# DIOT_PSU_integrated.net
KiCad netlist of a schematic drawn in Altium Designer
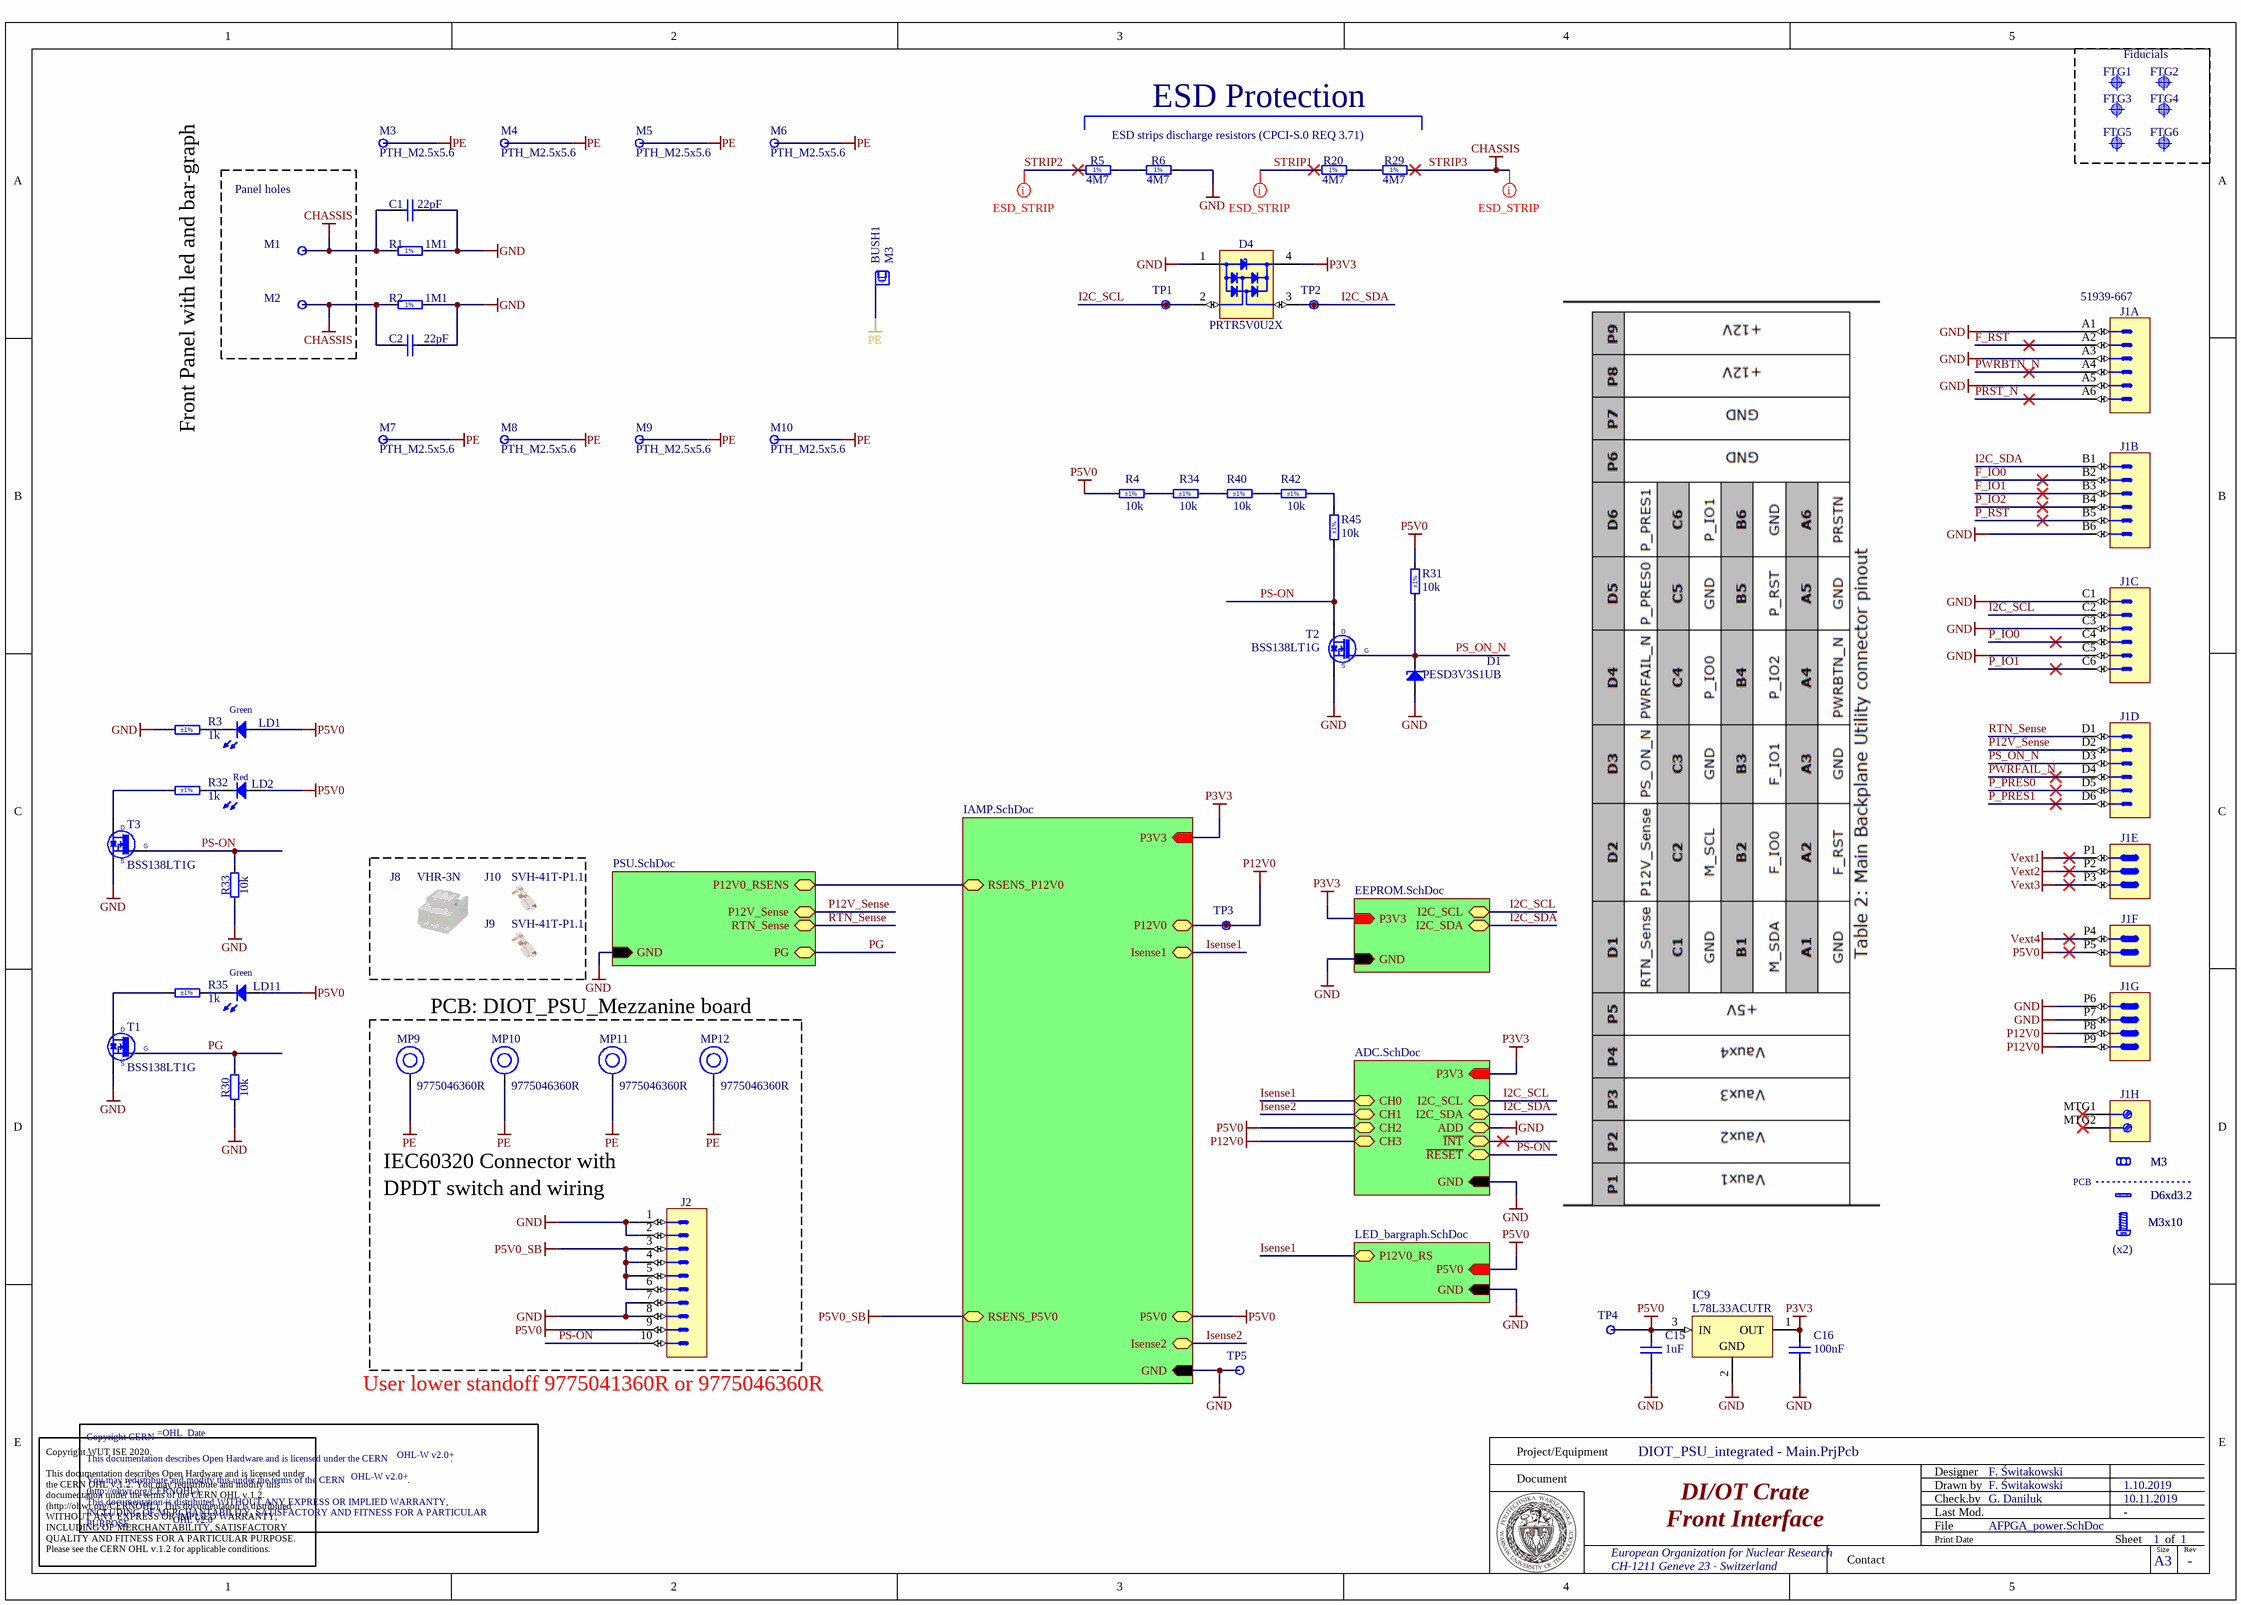
[diagram p0: DIOT_PSU_integrated.SchDoc]

(export (version "E")
  (design (tool "Eeschema 10.0.6"))
  (components
    (comp (ref "BUSH1")
      (value "M3")
      (footprint "WURTH_7461057")
      (description "Bush")
      (fields
        (field (name "PART NUMBER") "WURTH_7461057")
        (field (name "MANUFACTURER") "WURTH")
        (field (name "AUTHOR") "CERN DEM JLC")
      )
      (libsource (lib "Eletro-mechanical") (part "Bush"))
    )
    (comp (ref "C1")
      (value "22pF")
      (footprint "CAPC3216X180N")
      (description "Non-polarised capacitor")
      (fields
        (field (name "PART NUMBER") "CC1206_22PF_200V_1%_C0G_KEMET_C1206C220F2GAC")
        (field (name "VOLTAGE") "200V")
        (field (name "AUTHOR") "CERN DEM HF")
      )
      (libsource (lib "Capacitors") (part "Capacitor - non polarized"))
    )
    (comp (ref "C2")
      (value "22pF")
      (footprint "CAPC3216X180N")
      (description "Non-polarised capacitor")
      (fields
        (field (name "PART NUMBER") "CC1206_22PF_200V_1%_C0G_KEMET_C1206C220F2GAC")
        (field (name "VOLTAGE") "200V")
        (field (name "AUTHOR") "CERN DEM HF")
      )
      (libsource (lib "Capacitors") (part "Capacitor - non polarized"))
    )
    (comp (ref "C15")
      (value "1uF")
      (footprint "CAPC1608X87N")
      (description "Non-polarised capacitor")
      (fields
        (field (name "PART NUMBER") "CC0603_1UF_16V_10%_X7R")
        (field (name "VOLTAGE") "16V")
        (field (name "AUTHOR") "CERN DEM JLC")
      )
      (libsource (lib "Capacitors") (part "Capacitor - non polarized"))
    )
    (comp (ref "C16")
      (value "100nF")
      (footprint "CAPC1608X87N")
      (description "Non-polarised capacitor")
      (fields
        (field (name "PART NUMBER") "CC0603_100NF_50V_10%_X5R")
        (field (name "VOLTAGE") "50V")
        (field (name "AUTHOR") "CERN DEM MR")
      )
      (libsource (lib "Capacitors") (part "Capacitor - non polarized"))
    )
    (comp (ref "D1")
      (value "PESD3V3S1UB")
      (footprint "SODFL1608X65N")
      (description "ESD protection diode")
      (fields
        (field (name "VOLTAGE") "3V3")
        (field (name "POWER") "330W")
        (field (name "AUTHOR") "CERN DEM JLC")
      )
      (libsource (lib "ICs And Semiconductors") (part "Diode ESD"))
    )
    (comp (ref "D4")
      (value "PRTR5V0U2X")
      (footprint "SOT190P230X110-4N")
      (description "Ultra Low Capacitance Double Rail-to-Rail ESD Protection Diode")
      (fields
        (field (name "VOLTAGE") "5.5V")
        (field (name "MANUFACTURER") "NXP SEMICONDUCTORS")
        (field (name "AUTHOR") "CERN DEM JLC")
      )
      (libsource (lib "ICs And Semiconductors") (part "PRTR5V0U2X"))
    )
    (comp (ref "FTG1")
      (value "~")
      (footprint "FIDUCIAL_TOP_C100-200")
      (description "Fiducial Target")
      (fields (field (name "PART NUMBER") "FIDUCIAL_TARGET_C100-200") (field (name "AUTHOR") "CERN DEM JLC"))
      (libsource (lib "Eletro-mechanical") (part "Fiducial Target"))
    )
    (comp (ref "FTG2")
      (value "~")
      (footprint "FIDUCIAL_TOP_C100-200")
      (description "Fiducial Target")
      (fields (field (name "PART NUMBER") "FIDUCIAL_TARGET_C100-200") (field (name "AUTHOR") "CERN DEM JLC"))
      (libsource (lib "Eletro-mechanical") (part "Fiducial Target"))
    )
    (comp (ref "FTG3")
      (value "~")
      (footprint "FIDUCIAL_TOP_C100-200")
      (description "Fiducial Target")
      (fields (field (name "PART NUMBER") "FIDUCIAL_TARGET_C100-200") (field (name "AUTHOR") "CERN DEM JLC"))
      (libsource (lib "Eletro-mechanical") (part "Fiducial Target"))
    )
    (comp (ref "FTG4")
      (value "~")
      (footprint "FIDUCIAL_TOP_C100-200")
      (description "Fiducial Target")
      (fields (field (name "PART NUMBER") "FIDUCIAL_TARGET_C100-200") (field (name "AUTHOR") "CERN DEM JLC"))
      (libsource (lib "Eletro-mechanical") (part "Fiducial Target"))
    )
    (comp (ref "FTG5")
      (value "Use only in PCB")
      (footprint "FIDUCIAL_TOP_S100-200")
      (description "Fiducial Target")
      (fields (field (name "PART NUMBER") "FIDUCIAL_TARGET_S100-200") (field (name "AUTHOR") "CERN DEM JLC"))
      (libsource (lib "Eletro-mechanical") (part "Fiducial Target"))
    )
    (comp (ref "FTG6")
      (value "Use only in PCB")
      (footprint "FIDUCIAL_TOP_S100-200")
      (description "Fiducial Target")
      (fields (field (name "PART NUMBER") "FIDUCIAL_TARGET_S100-200") (field (name "AUTHOR") "CERN DEM JLC"))
      (libsource (lib "Eletro-mechanical") (part "Fiducial Target"))
    )
    (comp (ref "IC9")
      (value "L78L33ACUTR")
      (footprint "SOT89")
      (description "3-Terminal Regulator 1=OUT 2=GND 3=IN")
      (fields (field (name "MANUFACTURER") "ST MICROELECTRONICS") (field (name "AUTHOR") "CERN DEM JLC"))
      (libsource (lib "ICs And Semiconductors") (part "REG3 1OUT-2GND-3IN"))
    )
    (comp (ref "J1")
      (value "PwrBlade")
      (footprint "AMPHENOL_51939-667")
      (description "Thru-Hole, Lead 3.43mm, PowerBlade Right Angled Power Connector 3ACP 2P 24S 4P Contacts")
      (fields
        (field (name "PART NUMBER") "AMPHENOL_51939-667")
        (field (name "MANUFACTURER") "AMPHENOL")
        (field (name "MANUFACTURER PART NUMBER") "51939-667")
        (field (name "AUTHOR") "CERN DEM JLC")
      )
      (libsource (lib "Connectors") (part "AMPHENOL_51939-667"))
    )
    (comp (ref "J2")
      (value "Header 10")
      (footprint "SAMTEC_TSW-105-07-L-D-LL")
      (description "Connector 10 Male")
      (fields
        (field (name "PART NUMBER") "SAMTEC_TSW-105-07-L-D-LL")
        (field (name "MANUFACTURER") "SAMTEC")
        (field (name "AUTHOR") "CERN DEM JLC")
      )
      (libsource (lib "Connectors") (part "Connector 10 Male"))
    )
    (comp (ref "J8")
      (value "VHR-3N")
      (footprint "VHR-3N")
      (description "3 Rectangular Connectors - Housings Receptacle Natural 0.156\" (3.96mm)")
      (fields (field (name "MANUFACTURER") "JST Sales America Inc.") (field (name "AUTHOR") "LPA"))
      (libsource (lib "EDA-04213-V3-0_project") (part "VHR-3N"))
    )
    (comp (ref "J9")
      (value "SVH-41T-P1.1")
      (footprint "SVH-41T-P1.1")
      (description "Socket Contact Tin 16-20 AWG Crimp")
      (fields (field (name "MANUFACTURER") "JST Sales America Inc.") (field (name "AUTHOR") "LPA"))
      (libsource (lib "EDA-04213-V3-0_project") (part "SVH-41T-P1.1"))
    )
    (comp (ref "J10")
      (value "SVH-41T-P1.1")
      (footprint "SVH-41T-P1.1")
      (description "Socket Contact Tin 16-20 AWG Crimp")
      (fields (field (name "MANUFACTURER") "JST Sales America Inc.") (field (name "AUTHOR") "LPA"))
      (libsource (lib "EDA-04213-V3-0_project") (part "SVH-41T-P1.1"))
    )
    (comp (ref "LD1")
      (value "Green")
      (footprint "LED_AVAGO_HSME-C120")
      (description "LED Green 1C 2A")
      (fields
        (field (name "PART NUMBER") "LED_AVAGO_HSME-C120")
        (field (name "MANUFACTURER") "AVAGO TECHNOLOGIES")
        (field (name "AUTHOR") "CERN DEM JMW")
      )
      (libsource (lib "ICs And Semiconductors") (part "LED Green 1C 2A"))
    )
    (comp (ref "LD2")
      (value "Red")
      (footprint "LED_AVAGO_HSMC-C120")
      (description "LED Red 1C 2A")
      (fields
        (field (name "PART NUMBER") "LED_AVAGO_HSMC-C120")
        (field (name "MANUFACTURER") "AVAGO TECHNOLOGIES")
        (field (name "AUTHOR") "CERN DEM JMW")
      )
      (libsource (lib "ICs And Semiconductors") (part "LED Red 1C 2A"))
    )
    (comp (ref "LD11")
      (value "Green")
      (footprint "LED_AVAGO_HSME-C120")
      (description "LED Green 1C 2A")
      (fields
        (field (name "PART NUMBER") "LED_AVAGO_HSME-C120")
        (field (name "MANUFACTURER") "AVAGO TECHNOLOGIES")
        (field (name "AUTHOR") "CERN DEM JMW")
      )
      (libsource (lib "ICs And Semiconductors") (part "LED Green 1C 2A"))
    )
    (comp (ref "M1")
      (value "~")
      (footprint "MTG300_600")
      (description "Single Terminal Socket")
      (fields (field (name "PART NUMBER") "PLATED_HOLE3.0_PAD6.0") (field (name "AUTHOR") "CERN DEM JLC"))
      (libsource (lib "Eletro-mechanical") (part "Single Terminal Socket"))
    )
    (comp (ref "M2")
      (value "~")
      (footprint "MTG300_600")
      (description "Single Terminal Socket")
      (fields (field (name "PART NUMBER") "PLATED_HOLE3.0_PAD6.0") (field (name "AUTHOR") "CERN DEM JLC"))
      (libsource (lib "Eletro-mechanical") (part "Single Terminal Socket"))
    )
    (comp (ref "M3")
      (value "PTH_M2.5x5.6")
      (footprint "PTH_2,9x5.6")
      (description "Plated Hole for scre 2.5mm")
      (libsource (lib "TechnoSystem Workspace") (part "PTH_2.9x5.6"))
    )
    (comp (ref "M4")
      (value "PTH_M2.5x5.6")
      (footprint "PTH_2,9x5.6")
      (description "Plated Hole for scre 2.5mm")
      (libsource (lib "TechnoSystem Workspace") (part "PTH_2.9x5.6"))
    )
    (comp (ref "M5")
      (value "PTH_M2.5x5.6")
      (footprint "PTH_2,9x5.6")
      (description "Plated Hole for scre 2.5mm")
      (libsource (lib "TechnoSystem Workspace") (part "PTH_2.9x5.6"))
    )
    (comp (ref "M6")
      (value "PTH_M2.5x5.6")
      (footprint "PTH_2,9x5.6")
      (description "Plated Hole for scre 2.5mm")
      (libsource (lib "TechnoSystem Workspace") (part "PTH_2.9x5.6"))
    )
    (comp (ref "M7")
      (value "PTH_M2.5x5.6")
      (footprint "PTH_2,9x5.6")
      (description "Plated Hole for scre 2.5mm")
      (libsource (lib "TechnoSystem Workspace") (part "PTH_2.9x5.6"))
    )
    (comp (ref "M8")
      (value "PTH_M2.5x5.6")
      (footprint "PTH_2,9x5.6")
      (description "Plated Hole for scre 2.5mm")
      (libsource (lib "TechnoSystem Workspace") (part "PTH_2.9x5.6"))
    )
    (comp (ref "M9")
      (value "PTH_M2.5x5.6")
      (footprint "PTH_2,9x5.6")
      (description "Plated Hole for scre 2.5mm")
      (libsource (lib "TechnoSystem Workspace") (part "PTH_2.9x5.6"))
    )
    (comp (ref "M10")
      (value "PTH_M2.5x5.6")
      (footprint "PTH_2,9x5.6")
      (description "Plated Hole for scre 2.5mm")
      (libsource (lib "TechnoSystem Workspace") (part "PTH_2.9x5.6"))
    )
    (comp (ref "MP9")
      (value "9775046360R")
      (footprint "9775046360")
      (description "WA-SMSR SMT Steel Spacer, Reverse M3 non Stop")
      (libsource (lib "TechnoSystem Workspace") (part "Spacer"))
    )
    (comp (ref "MP10")
      (value "9775046360R")
      (footprint "9775046360")
      (description "WA-SMSR SMT Steel Spacer, Reverse M3 non Stop")
      (libsource (lib "TechnoSystem Workspace") (part "Spacer"))
    )
    (comp (ref "MP11")
      (value "9775046360R")
      (footprint "9775046360")
      (description "WA-SMSR SMT Steel Spacer, Reverse M3 non Stop")
      (libsource (lib "TechnoSystem Workspace") (part "Spacer"))
    )
    (comp (ref "MP12")
      (value "9775046360R")
      (footprint "9775046360")
      (description "WA-SMSR SMT Steel Spacer, Reverse M3 non Stop")
      (libsource (lib "TechnoSystem Workspace") (part "Spacer"))
    )
    (comp (ref "NUT1")
      (value "M3")
      (footprint "BOSSARD_BN628-1241443_v")
      (description "Nut")
      (fields
        (field (name "PART NUMBER") "BOSSARD_BN628-1241443_v")
        (field (name "MANUFACTURER") "BOSSARD")
        (field (name "AUTHOR") "CERN DEM JMW")
      )
      (libsource (lib "Eletro-mechanical") (part "Nut"))
    )
    (comp (ref "NUT2")
      (value "M3")
      (footprint "BOSSARD_BN628-1241443_v")
      (description "Nut")
      (fields
        (field (name "PART NUMBER") "BOSSARD_BN628-1241443_v")
        (field (name "MANUFACTURER") "BOSSARD")
        (field (name "AUTHOR") "CERN DEM JMW")
      )
      (libsource (lib "Eletro-mechanical") (part "Nut"))
    )
    (comp (ref "OHL1")
      (value "CERN_OHL")
      (footprint "CERN_OHL")
      (fields (field (name "AUTHOR") "CERN DEM HF"))
      (libsource (lib "Eletro-mechanical") (part "CERN_OHL"))
    )
    (comp (ref "R1")
      (value "1M1")
      (footprint "RESC2012X60N")
      (description "Resistor - 1%")
      (fields
        (field (name "PART NUMBER") "R0805_1M1_1%_0.125W_100PPM")
        (field (name "POWER") "0.125W")
        (field (name "AUTHOR") "CERN DEM JLC")
      )
      (libsource (lib "") (part "Resistor - 1%_1"))
    )
    (comp (ref "R2")
      (value "1M1")
      (footprint "RESC2012X60N")
      (description "Resistor - 1%")
      (fields
        (field (name "PART NUMBER") "R0805_1M1_1%_0.125W_100PPM")
        (field (name "POWER") "0.125W")
        (field (name "AUTHOR") "CERN DEM JLC")
      )
      (libsource (lib "") (part "Resistor - 1%_1"))
    )
    (comp (ref "R3")
      (value "1k")
      (footprint "RESC1608X55N")
      (description "Resistor - 1%")
      (fields
        (field (name "TOLERANCE") "±1%")
        (field (name "PART NUMBER") "R0603_1K_1%_0.1W_100PPM")
        (field (name "POWER") "0.1W")
        (field (name "AUTHOR") "CERN DEM JLC")
      )
      (libsource (lib "Resistors") (part "Resistor - 1%"))
    )
    (comp (ref "R4")
      (value "10k")
      (footprint "RESC1608X55N")
      (description "Resistor - 1%")
      (fields
        (field (name "TOLERANCE") "±1%")
        (field (name "PART NUMBER") "R0603_10K_1%_0.1W_100PPM")
        (field (name "POWER") "0.1W")
        (field (name "AUTHOR") "CERN DEM JLC")
      )
      (libsource (lib "Resistors") (part "Resistor - 1%"))
    )
    (comp (ref "R5")
      (value "4M7")
      (footprint "RESC2113X55N")
      (description "Resistor - 1%")
      (fields
        (field (name "PART NUMBER") "R0805_4M7_1%_0.125W_100PPM_VISHAY_CRCW e3")
        (field (name "POWER") "0.125W")
        (field (name "AUTHOR") "CERN DEM BR")
      )
      (libsource (lib "") (part "Resistor - 1%_1"))
    )
    (comp (ref "R6")
      (value "4M7")
      (footprint "RESC2113X55N")
      (description "Resistor - 1%")
      (fields
        (field (name "PART NUMBER") "R0805_4M7_1%_0.125W_100PPM_VISHAY_CRCW e3")
        (field (name "POWER") "0.125W")
        (field (name "AUTHOR") "CERN DEM BR")
      )
      (libsource (lib "") (part "Resistor - 1%_1"))
    )
    (comp (ref "R20")
      (value "4M7")
      (footprint "RESC2113X55N")
      (description "Resistor - 1%")
      (fields
        (field (name "PART NUMBER") "R0805_4M7_1%_0.125W_100PPM_VISHAY_CRCW e3")
        (field (name "POWER") "0.125W")
        (field (name "AUTHOR") "CERN DEM BR")
      )
      (libsource (lib "") (part "Resistor - 1%_1"))
    )
    (comp (ref "R29")
      (value "4M7")
      (footprint "RESC2113X55N")
      (description "Resistor - 1%")
      (fields
        (field (name "PART NUMBER") "R0805_4M7_1%_0.125W_100PPM_VISHAY_CRCW e3")
        (field (name "POWER") "0.125W")
        (field (name "AUTHOR") "CERN DEM BR")
      )
      (libsource (lib "") (part "Resistor - 1%_1"))
    )
    (comp (ref "R30")
      (value "10k")
      (footprint "RESC1608X55N")
      (description "Resistor - 1%")
      (fields
        (field (name "PART NUMBER") "R0603_10K_1%_0.1W_100PPM")
        (field (name "POWER") "0.1W")
        (field (name "AUTHOR") "CERN DEM JLC")
      )
      (libsource (lib "Resistors") (part "Resistor - 1%"))
    )
    (comp (ref "R31")
      (value "10k")
      (footprint "RESC1608X55N")
      (description "Resistor - 1%")
      (fields
        (field (name "TOLERANCE") "±1%")
        (field (name "PART NUMBER") "R0603_10K_1%_0.1W_100PPM")
        (field (name "POWER") "0.1W")
        (field (name "AUTHOR") "CERN DEM JLC")
      )
      (libsource (lib "Resistors") (part "Resistor - 1%"))
    )
    (comp (ref "R32")
      (value "1k")
      (footprint "RESC1608X55N")
      (description "Resistor - 1%")
      (fields
        (field (name "TOLERANCE") "±1%")
        (field (name "PART NUMBER") "R0603_1K_1%_0.1W_100PPM")
        (field (name "POWER") "0.1W")
        (field (name "AUTHOR") "CERN DEM JLC")
      )
      (libsource (lib "Resistors") (part "Resistor - 1%"))
    )
    (comp (ref "R33")
      (value "10k")
      (footprint "RESC1608X55N")
      (description "Resistor - 1%")
      (fields
        (field (name "PART NUMBER") "R0603_10K_1%_0.1W_100PPM")
        (field (name "POWER") "0.1W")
        (field (name "AUTHOR") "CERN DEM JLC")
      )
      (libsource (lib "Resistors") (part "Resistor - 1%"))
    )
    (comp (ref "R34")
      (value "10k")
      (footprint "RESC1608X55N")
      (description "Resistor - 1%")
      (fields
        (field (name "TOLERANCE") "±1%")
        (field (name "PART NUMBER") "R0603_10K_1%_0.1W_100PPM")
        (field (name "POWER") "0.1W")
        (field (name "AUTHOR") "CERN DEM JLC")
      )
      (libsource (lib "Resistors") (part "Resistor - 1%"))
    )
    (comp (ref "R35")
      (value "1k")
      (footprint "RESC1608X55N")
      (description "Resistor - 1%")
      (fields
        (field (name "TOLERANCE") "±1%")
        (field (name "PART NUMBER") "R0603_1K_1%_0.1W_100PPM")
        (field (name "POWER") "0.1W")
        (field (name "AUTHOR") "CERN DEM JLC")
      )
      (libsource (lib "Resistors") (part "Resistor - 1%"))
    )
    (comp (ref "R40")
      (value "10k")
      (footprint "RESC1608X55N")
      (description "Resistor - 1%")
      (fields
        (field (name "TOLERANCE") "±1%")
        (field (name "PART NUMBER") "R0603_10K_1%_0.1W_100PPM")
        (field (name "POWER") "0.1W")
        (field (name "AUTHOR") "CERN DEM JLC")
      )
      (libsource (lib "Resistors") (part "Resistor - 1%"))
    )
    (comp (ref "R42")
      (value "10k")
      (footprint "RESC1608X55N")
      (description "Resistor - 1%")
      (fields
        (field (name "TOLERANCE") "±1%")
        (field (name "PART NUMBER") "R0603_10K_1%_0.1W_100PPM")
        (field (name "POWER") "0.1W")
        (field (name "AUTHOR") "CERN DEM JLC")
      )
      (libsource (lib "Resistors") (part "Resistor - 1%"))
    )
    (comp (ref "R45")
      (value "10k")
      (footprint "RESC1608X55N")
      (description "Resistor - 1%")
      (fields
        (field (name "TOLERANCE") "±1%")
        (field (name "PART NUMBER") "R0603_10K_1%_0.1W_100PPM")
        (field (name "POWER") "0.1W")
        (field (name "AUTHOR") "CERN DEM JLC")
      )
      (libsource (lib "Resistors") (part "Resistor - 1%"))
    )
    (comp (ref "SCREW1")
      (value "M3x10")
      (footprint "BOSSARD_BN5687-3061608_v")
      (description "Screw")
      (fields
        (field (name "PART NUMBER") "BOSSARD_BN5687-3061608_v")
        (field (name "MANUFACTURER") "BOSSARD")
        (field (name "AUTHOR") "CERN DEM JLC")
      )
      (libsource (lib "Eletro-mechanical") (part "Screw"))
    )
    (comp (ref "SCREW2")
      (value "M3x10")
      (footprint "BOSSARD_BN5687-3061608_v")
      (description "Screw")
      (fields
        (field (name "PART NUMBER") "BOSSARD_BN5687-3061608_v")
        (field (name "MANUFACTURER") "BOSSARD")
        (field (name "AUTHOR") "CERN DEM JLC")
      )
      (libsource (lib "Eletro-mechanical") (part "Screw"))
    )
    (comp (ref "T1")
      (value "BSS138LT1G")
      (footprint "SOT95P240X110-3N")
      (description "N-CHANNEL MOSFET WITH DIODE")
      (fields (field (name "MANUFACTURER") "ON SEMICONDUCTOR") (field (name "AUTHOR") "CERN DEM JLC"))
      (libsource (lib "ICs And Semiconductors") (part "N-MOSFET-D 1G 2S 3D"))
    )
    (comp (ref "T2")
      (value "BSS138LT1G")
      (footprint "SOT95P240X110-3N")
      (description "N-CHANNEL MOSFET WITH DIODE")
      (fields
        (field (name "MANUFACTURER") "ON SEMICONDUCTOR")
        (field (name "MANUFACTURER PART NUMBER") "BSS138L")
        (field (name "AUTHOR") "CERN DEM JLC")
      )
      (libsource (lib "ICs And Semiconductors") (part "N-MOSFET-D 1G 2S 3D"))
    )
    (comp (ref "T3")
      (value "BSS138LT1G")
      (footprint "SOT95P240X110-3N")
      (description "N-CHANNEL MOSFET WITH DIODE")
      (fields (field (name "MANUFACTURER") "ON SEMICONDUCTOR") (field (name "AUTHOR") "CERN DEM JLC"))
      (libsource (lib "ICs And Semiconductors") (part "N-MOSFET-D 1G 2S 3D"))
    )
    (comp (ref "TP1")
      (value "Test Point")
      (footprint "TPS127")
      (fields (field (name "PART NUMBER") "SMD_PAD_1.27X1.27MM") (field (name "AUTHOR") "CERN DEM JLC"))
      (libsource (lib "Eletro-mechanical") (part "Test Point"))
    )
    (comp (ref "TP2")
      (value "Test Point")
      (footprint "TPS127")
      (fields (field (name "PART NUMBER") "SMD_PAD_1.27X1.27MM") (field (name "AUTHOR") "CERN DEM JLC"))
      (libsource (lib "Eletro-mechanical") (part "Test Point"))
    )
    (comp (ref "TP3")
      (value "Test Point")
      (footprint "TPS127")
      (fields (field (name "PART NUMBER") "SMD_PAD_1.27X1.27MM") (field (name "AUTHOR") "CERN DEM JLC"))
      (libsource (lib "Eletro-mechanical") (part "Test Point"))
    )
    (comp (ref "TP4")
      (value "Test Point")
      (footprint "TPS127")
      (fields (field (name "PART NUMBER") "SMD_PAD_1.27X1.27MM") (field (name "AUTHOR") "CERN DEM JLC"))
      (libsource (lib "Eletro-mechanical") (part "Test Point"))
    )
    (comp (ref "TP5")
      (value "Test Point")
      (footprint "TPS127")
      (fields (field (name "PART NUMBER") "SMD_PAD_1.27X1.27MM") (field (name "AUTHOR") "CERN DEM JLC"))
      (libsource (lib "Eletro-mechanical") (part "Test Point"))
    )
    (comp (ref "WASHER1")
      (value "D6xd3.2")
      (footprint "BOSSARD_BN83728-8243964_v")
      (description "Washer")
      (fields
        (field (name "PART NUMBER") "BOSSARD_BN83728-8243964_v")
        (field (name "MANUFACTURER") "BOSSARD")
        (field (name "AUTHOR") "CERN DEM JLC")
      )
      (libsource (lib "Eletro-mechanical") (part "Washer"))
    )
    (comp (ref "WASHER2")
      (value "D6xd3.2")
      (footprint "BOSSARD_BN83728-8243964_v")
      (description "Washer")
      (fields
        (field (name "PART NUMBER") "BOSSARD_BN83728-8243964_v")
        (field (name "MANUFACTURER") "BOSSARD")
        (field (name "AUTHOR") "CERN DEM JLC")
      )
      (libsource (lib "Eletro-mechanical") (part "Washer"))
    )
  )
  (nets
    (net (code "1") (name "/F_IO0") (class "Default")
      (node (ref "J1") (pin "B2") (pinfunction "B2_B2") (pintype "bidirectional"))
    )
    (net (code "2") (name "/F_IO1") (class "Default")
      (node (ref "J1") (pin "B3") (pinfunction "B3_B3") (pintype "bidirectional"))
    )
    (net (code "3") (name "/F_RST") (class "Default")
      (node (ref "J1") (pin "A2") (pinfunction "A2_A2") (pintype "bidirectional"))
    )
    (net (code "4") (name "/I2C_SCL") (class "Default")
      (node (ref "D4") (pin "2") (pinfunction "I/O1_2") (pintype "bidirectional"))
      (node (ref "J1") (pin "C2") (pinfunction "C2_C2") (pintype "bidirectional"))
      (node (ref "TP1") (pin "1") (pinfunction "1_1") (pintype "bidirectional"))
    )
    (net (code "5") (name "/I2C_SDA") (class "Default")
      (node (ref "D4") (pin "3") (pinfunction "I/O2_3") (pintype "bidirectional"))
      (node (ref "J1") (pin "B1") (pinfunction "B1_B1") (pintype "bidirectional"))
      (node (ref "TP2") (pin "1") (pinfunction "1_1") (pintype "bidirectional"))
    )
    (net (code "9") (name "/P12V_Sense") (class "Default")
      (node (ref "J1") (pin "D2") (pinfunction "D2_D2") (pintype "bidirectional"))
    )
    (net (code "10") (name "/PG") (class "Default")
      (node (ref "R30") (pin "2") (pinfunction "2_2") (pintype "passive"))
      (node (ref "T1") (pin "1") (pinfunction "G_1") (pintype "passive"))
    )
    (net (code "11") (name "/PRST_N") (class "Default")
      (node (ref "J1") (pin "A6") (pinfunction "A6_A6") (pintype "bidirectional"))
    )
    (net (code "12") (name "/PS-ON") (class "Default")
      (node (ref "J2") (pin "10") (pinfunction "10_10") (pintype "bidirectional"))
      (node (ref "R33") (pin "2") (pinfunction "2_2") (pintype "passive"))
      (node (ref "R45") (pin "1") (pinfunction "1_1") (pintype "passive"))
      (node (ref "T2") (pin "3") (pinfunction "D_3") (pintype "passive"))
      (node (ref "T3") (pin "1") (pinfunction "G_1") (pintype "passive"))
    )
    (net (code "13") (name "/PS_ON_N") (class "Default")
      (node (ref "D1") (pin "1") (pinfunction "C_1") (pintype "passive"))
      (node (ref "J1") (pin "D3") (pinfunction "D3_D3") (pintype "bidirectional"))
      (node (ref "R31") (pin "1") (pinfunction "1_1") (pintype "passive"))
      (node (ref "T2") (pin "1") (pinfunction "G_1") (pintype "passive"))
    )
    (net (code "14") (name "/PWRBTN_N") (class "Default")
      (node (ref "J1") (pin "A4") (pinfunction "A4_A4") (pintype "bidirectional"))
    )
    (net (code "15") (name "/PWRFAIL_N") (class "Default")
      (node (ref "J1") (pin "D4") (pinfunction "D4_D4") (pintype "bidirectional"))
    )
    (net (code "16") (name "/P_IO0") (class "Default")
      (node (ref "J1") (pin "C4") (pinfunction "C4_C4") (pintype "bidirectional"))
    )
    (net (code "17") (name "/P_IO1") (class "Default")
      (node (ref "J1") (pin "C6") (pinfunction "C6_C6") (pintype "bidirectional"))
    )
    (net (code "18") (name "/P_IO2") (class "Default")
      (node (ref "J1") (pin "B4") (pinfunction "B4_B4") (pintype "bidirectional"))
    )
    (net (code "19") (name "/P_PRES0") (class "Default")
      (node (ref "J1") (pin "D5") (pinfunction "D5_D5") (pintype "bidirectional"))
    )
    (net (code "20") (name "/P_PRES1") (class "Default")
      (node (ref "J1") (pin "D6") (pinfunction "D6_D6") (pintype "bidirectional"))
    )
    (net (code "21") (name "/P_RST") (class "Default")
      (node (ref "J1") (pin "B5") (pinfunction "B5_B5") (pintype "bidirectional"))
    )
    (net (code "22") (name "/RTN_Sense") (class "Default")
      (node (ref "J1") (pin "D1") (pinfunction "D1_D1") (pintype "bidirectional"))
    )
    (net (code "23") (name "/STRIP1") (class "Default")
      (node (ref "R20") (pin "1") (pinfunction "1_1") (pintype "passive+no_connect"))
    )
    (net (code "24") (name "/STRIP2") (class "Default")
      (node (ref "R5") (pin "1") (pinfunction "1_1") (pintype "passive+no_connect"))
    )
    (net (code "26") (name "CHASSIS") (class "Default")
      (node (ref "C1") (pin "1") (pinfunction "1_1") (pintype "passive"))
      (node (ref "C2") (pin "1") (pinfunction "1_1") (pintype "passive"))
      (node (ref "M1") (pin "1") (pinfunction "1_1") (pintype "bidirectional"))
      (node (ref "M2") (pin "1") (pinfunction "1_1") (pintype "bidirectional"))
      (node (ref "R1") (pin "1") (pinfunction "1_1") (pintype "passive"))
      (node (ref "R2") (pin "1") (pinfunction "1_1") (pintype "passive"))
      (node (ref "R29") (pin "2") (pinfunction "2_2") (pintype "passive"))
    )
    (net (code "27") (name "GND") (class "Default")
      (node (ref "C1") (pin "2") (pinfunction "2_2") (pintype "passive"))
      (node (ref "C15") (pin "1") (pinfunction "1_1") (pintype "passive"))
      (node (ref "C16") (pin "2") (pinfunction "2_2") (pintype "passive"))
      (node (ref "C2") (pin "2") (pinfunction "2_2") (pintype "passive"))
      (node (ref "D1") (pin "2") (pinfunction "A_2") (pintype "passive"))
      (node (ref "D4") (pin "1") (pinfunction "GND_1") (pintype "power_in"))
      (node (ref "IC9") (pin "2") (pinfunction "GND_2") (pintype "power_in"))
      (node (ref "J1") (pin "A1") (pinfunction "A1_A1") (pintype "bidirectional"))
      (node (ref "J1") (pin "A3") (pinfunction "A3_A3") (pintype "bidirectional"))
      (node (ref "J1") (pin "A5") (pinfunction "A5_A5") (pintype "bidirectional"))
      (node (ref "J1") (pin "B6") (pinfunction "B6_B6") (pintype "bidirectional"))
      (node (ref "J1") (pin "C1") (pinfunction "C1_C1") (pintype "bidirectional"))
      (node (ref "J1") (pin "C3") (pinfunction "C3_C3") (pintype "bidirectional"))
      (node (ref "J1") (pin "C5") (pinfunction "C5_C5") (pintype "bidirectional"))
      (node (ref "J1") (pin "P6") (pinfunction "P6_P6") (pintype "bidirectional"))
      (node (ref "J1") (pin "P7") (pinfunction "P7_P7") (pintype "bidirectional"))
      (node (ref "J2") (pin "1") (pinfunction "1_1") (pintype "bidirectional"))
      (node (ref "J2") (pin "2") (pinfunction "2_2") (pintype "bidirectional"))
      (node (ref "J2") (pin "7") (pinfunction "7_7") (pintype "bidirectional"))
      (node (ref "J2") (pin "8") (pinfunction "8_8") (pintype "bidirectional"))
      (node (ref "R1") (pin "2") (pinfunction "2_2") (pintype "passive"))
      (node (ref "R2") (pin "2") (pinfunction "2_2") (pintype "passive"))
      (node (ref "R3") (pin "1") (pinfunction "1_1") (pintype "passive"))
      (node (ref "R30") (pin "1") (pinfunction "1_1") (pintype "passive"))
      (node (ref "R33") (pin "1") (pinfunction "1_1") (pintype "passive"))
      (node (ref "R6") (pin "2") (pinfunction "2_2") (pintype "passive"))
      (node (ref "T1") (pin "2") (pinfunction "S_2") (pintype "passive"))
      (node (ref "T2") (pin "2") (pinfunction "S_2") (pintype "passive"))
      (node (ref "T3") (pin "2") (pinfunction "S_2") (pintype "passive"))
      (node (ref "TP5") (pin "1") (pinfunction "1_1") (pintype "bidirectional"))
    )
    (net (code "28") (name "Net-(LD1-C)") (class "Default")
      (node (ref "LD1") (pin "1") (pinfunction "C_1") (pintype "passive"))
      (node (ref "R3") (pin "2") (pinfunction "2_2") (pintype "passive"))
    )
    (net (code "29") (name "Net-(LD2-C)") (class "Default")
      (node (ref "LD2") (pin "1") (pinfunction "C_1") (pintype "passive"))
      (node (ref "R32") (pin "2") (pinfunction "2_2") (pintype "passive"))
    )
    (net (code "30") (name "Net-(LD11-C)") (class "Default")
      (node (ref "LD11") (pin "1") (pinfunction "C_1") (pintype "passive"))
      (node (ref "R35") (pin "2") (pinfunction "2_2") (pintype "passive"))
    )
    (net (code "31") (name "Net-(R5-Pad2)") (class "Default")
      (node (ref "R5") (pin "2") (pinfunction "2_2") (pintype "passive"))
      (node (ref "R6") (pin "1") (pinfunction "1_1") (pintype "passive"))
    )
    (net (code "32") (name "Net-(R20-Pad2)") (class "Default")
      (node (ref "R20") (pin "2") (pinfunction "2_2") (pintype "passive"))
      (node (ref "R29") (pin "1") (pinfunction "1_1") (pintype "passive"))
    )
    (net (code "33") (name "Net-(R34-Pad1)") (class "Default")
      (node (ref "R34") (pin "1") (pinfunction "1_1") (pintype "passive"))
      (node (ref "R4") (pin "1") (pinfunction "1_1") (pintype "passive"))
    )
    (net (code "34") (name "Net-(R34-Pad2)") (class "Default")
      (node (ref "R34") (pin "2") (pinfunction "2_2") (pintype "passive"))
      (node (ref "R40") (pin "2") (pinfunction "2_2") (pintype "passive"))
    )
    (net (code "35") (name "Net-(R40-Pad1)") (class "Default")
      (node (ref "R40") (pin "1") (pinfunction "1_1") (pintype "passive"))
      (node (ref "R42") (pin "1") (pinfunction "1_1") (pintype "passive"))
    )
    (net (code "36") (name "Net-(R42-Pad2)") (class "Default")
      (node (ref "R42") (pin "2") (pinfunction "2_2") (pintype "passive"))
      (node (ref "R45") (pin "2") (pinfunction "2_2") (pintype "passive"))
    )
    (net (code "37") (name "Net-(T1-D)") (class "Default")
      (node (ref "R35") (pin "1") (pinfunction "1_1") (pintype "passive"))
      (node (ref "T1") (pin "3") (pinfunction "D_3") (pintype "passive"))
    )
    (net (code "38") (name "Net-(T3-D)") (class "Default")
      (node (ref "R32") (pin "1") (pinfunction "1_1") (pintype "passive"))
      (node (ref "T3") (pin "3") (pinfunction "D_3") (pintype "passive"))
    )
    (net (code "39") (name "P3V3") (class "Default")
      (node (ref "C16") (pin "1") (pinfunction "1_1") (pintype "passive"))
      (node (ref "D4") (pin "4") (pinfunction "VCC_4") (pintype "power_in"))
      (node (ref "IC9") (pin "1") (pinfunction "OUT_1") (pintype "power_in"))
    )
    (net (code "40") (name "P5V0") (class "Default")
      (node (ref "C15") (pin "2") (pinfunction "2_2") (pintype "passive"))
      (node (ref "IC9") (pin "3") (pinfunction "IN_3") (pintype "input"))
      (node (ref "J1") (pin "P5") (pinfunction "P5_P5") (pintype "bidirectional"))
      (node (ref "J2") (pin "9") (pinfunction "9_9") (pintype "bidirectional"))
      (node (ref "LD1") (pin "2") (pinfunction "A_2") (pintype "passive"))
      (node (ref "LD11") (pin "2") (pinfunction "A_2") (pintype "passive"))
      (node (ref "LD2") (pin "2") (pinfunction "A_2") (pintype "passive"))
      (node (ref "R31") (pin "2") (pinfunction "2_2") (pintype "passive"))
      (node (ref "R4") (pin "2") (pinfunction "2_2") (pintype "passive"))
      (node (ref "TP4") (pin "1") (pinfunction "1_1") (pintype "bidirectional"))
    )
    (net (code "41") (name "P5V0_SB") (class "Default")
      (node (ref "J2") (pin "3") (pinfunction "3_3") (pintype "bidirectional"))
      (node (ref "J2") (pin "4") (pinfunction "4_4") (pintype "bidirectional"))
      (node (ref "J2") (pin "5") (pinfunction "5_5") (pintype "bidirectional"))
      (node (ref "J2") (pin "6") (pinfunction "6_6") (pintype "bidirectional"))
    )
    (net (code "42") (name "P12V0") (class "Default")
      (node (ref "J1") (pin "P8") (pinfunction "P8_P8") (pintype "bidirectional"))
      (node (ref "J1") (pin "P9") (pinfunction "P9_P9") (pintype "bidirectional"))
      (node (ref "TP3") (pin "1") (pinfunction "1_1") (pintype "bidirectional"))
    )
    (net (code "43") (name "PE") (class "Default")
      (node (ref "BUSH1") (pin "1") (pinfunction "1_1") (pintype "bidirectional"))
      (node (ref "M10") (pin "1") (pinfunction "1_1") (pintype "bidirectional"))
      (node (ref "M3") (pin "1") (pinfunction "1_1") (pintype "bidirectional"))
      (node (ref "M4") (pin "1") (pinfunction "1_1") (pintype "bidirectional"))
      (node (ref "M5") (pin "1") (pinfunction "1_1") (pintype "bidirectional"))
      (node (ref "M6") (pin "1") (pinfunction "1_1") (pintype "bidirectional"))
      (node (ref "M7") (pin "1") (pinfunction "1_1") (pintype "bidirectional"))
      (node (ref "M8") (pin "1") (pinfunction "1_1") (pintype "bidirectional"))
      (node (ref "M9") (pin "1") (pinfunction "1_1") (pintype "bidirectional"))
      (node (ref "MP10") (pin "1") (pinfunction "1_1") (pintype "passive"))
      (node (ref "MP11") (pin "1") (pinfunction "1_1") (pintype "passive"))
      (node (ref "MP12") (pin "1") (pinfunction "1_1") (pintype "passive"))
      (node (ref "MP9") (pin "1") (pinfunction "1_1") (pintype "passive"))
    )
    (net (code "44") (name "Vext1") (class "Default")
      (node (ref "J1") (pin "P1") (pinfunction "P1_P1") (pintype "bidirectional"))
    )
    (net (code "45") (name "Vext2") (class "Default")
      (node (ref "J1") (pin "P2") (pinfunction "P2_P2") (pintype "bidirectional"))
    )
    (net (code "46") (name "Vext3") (class "Default")
      (node (ref "J1") (pin "P3") (pinfunction "P3_P3") (pintype "bidirectional"))
    )
    (net (code "47") (name "Vext4") (class "Default")
      (node (ref "J1") (pin "P4") (pinfunction "P4_P4") (pintype "bidirectional"))
    )
    (net (code "48") (name "unconnected-(J1-PadMTG1)") (class "Default")
      (node (ref "J1") (pin "MTG1") (pinfunction "MTG1_MTG1") (pintype "passive+no_connect"))
    )
    (net (code "49") (name "unconnected-(J1-PadMTG2)") (class "Default")
      (node (ref "J1") (pin "MTG2") (pinfunction "MTG2_MTG2") (pintype "passive+no_connect"))
    )
  )
)
